# Board_2550.net
KiCad netlist of a schematic drawn in EAGLE
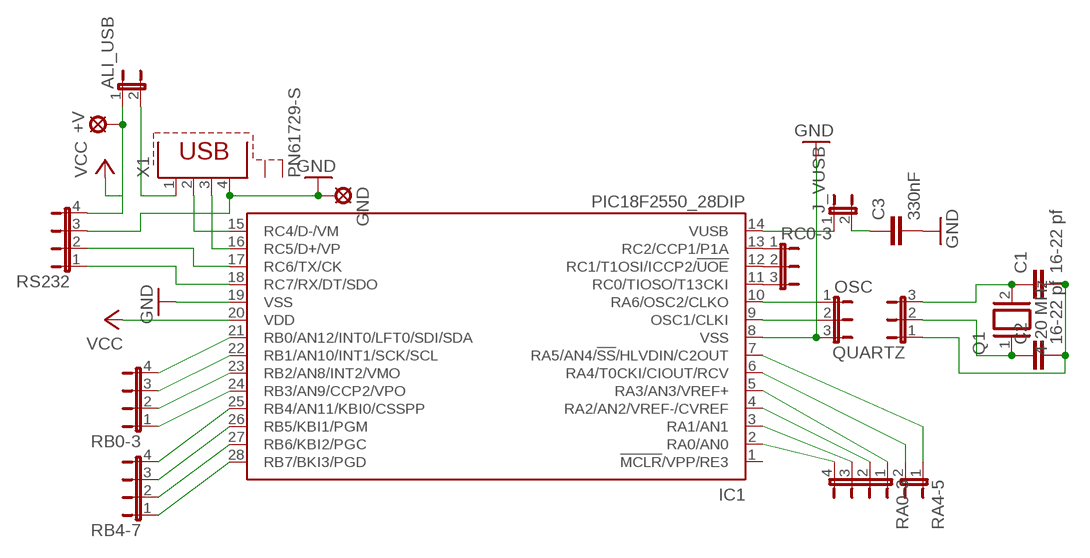
[diagram p0: schematic, sheet 1]

(export (version "E")
  (design (tool "Eeschema 10.0.6"))
  (components
    (comp (ref "+V")
      (value "SE14")
      (footprint "eagle-import:SE14")
      (libsource (lib "eagle-import") (part "SE14"))
    )
    (comp (ref "ALI_USB")
      (value "JP1E")
      (footprint "eagle-import:JP1")
      (libsource (lib "eagle-import") (part "JP1E"))
    )
    (comp (ref "C1")
      (value "16-22 pf")
      (footprint "eagle-import:C025-024X044")
      (libsource (lib "eagle-import") (part "C-EU025-024X044"))
    )
    (comp (ref "C2")
      (value "16-22 pf")
      (footprint "eagle-import:C025-024X044")
      (libsource (lib "eagle-import") (part "C-EU025-024X044"))
    )
    (comp (ref "C3")
      (value "330nF")
      (footprint "eagle-import:C025-024X044")
      (libsource (lib "eagle-import") (part "C-EU025-024X044"))
    )
    (comp (ref "GND")
      (value "SE14")
      (footprint "eagle-import:SE14")
      (libsource (lib "eagle-import") (part "SE14"))
    )
    (comp (ref "IC1")
      (value "PIC18F2550_28DIP")
      (footprint "eagle-import:DIL28-3")
      (fields (field (name "MF") "MICROCHIP") (field (name "MPN") "PIC18F2550-I/SP"))
      (libsource (lib "eagle-import") (part "PIC18F2_28DIP550"))
    )
    (comp (ref "J_VUSB")
      (value "JP1E")
      (footprint "eagle-import:JP1")
      (libsource (lib "eagle-import") (part "JP1E"))
    )
    (comp (ref "OSC")
      (value "JP2E")
      (footprint "eagle-import:JP2")
      (libsource (lib "eagle-import") (part "JP2E"))
    )
    (comp (ref "Q1")
      (value "4-20 MHz")
      (footprint "eagle-import:Q")
      (libsource (lib "eagle-import") (part "XTAL"))
    )
    (comp (ref "QUARTZ")
      (value "JP2W")
      (footprint "eagle-import:JP2W")
      (libsource (lib "eagle-import") (part "JP2W"))
    )
    (comp (ref "RA0-3")
      (value "JP4E")
      (footprint "eagle-import:JP4")
      (libsource (lib "eagle-import") (part "JP4E"))
    )
    (comp (ref "RA4-5")
      (value "JP1E")
      (footprint "eagle-import:JP1")
      (libsource (lib "eagle-import") (part "JP1E"))
    )
    (comp (ref "RB0-3")
      (value "JP4E")
      (footprint "eagle-import:JP4")
      (libsource (lib "eagle-import") (part "JP4E"))
    )
    (comp (ref "RB4-7")
      (value "JP4E")
      (footprint "eagle-import:JP4")
      (libsource (lib "eagle-import") (part "JP4E"))
    )
    (comp (ref "RC0-3")
      (value "JP2E")
      (footprint "eagle-import:JP2")
      (libsource (lib "eagle-import") (part "JP2E"))
    )
    (comp (ref "RS232")
      (value "JP4E")
      (footprint "eagle-import:JP4")
      (libsource (lib "eagle-import") (part "JP4E"))
    )
    (comp (ref "X1")
      (value "PN61729-S")
      (footprint "eagle-import:PN61729-S")
      (libsource (lib "eagle-import") (part "PN61729-S"))
    )
  )
  (nets
    (net (code "1") (name "GND") (class "Default")
      (node (ref "C3") (pin "2") (pinfunction "2_2") (pintype "passive"))
      (node (ref "GND") (pin "MP") (pinfunction "MP_MP") (pintype "passive"))
      (node (ref "IC1") (pin "19") (pinfunction "VSS_19") (pintype "power_in"))
      (node (ref "IC1") (pin "8") (pinfunction "VSS_8") (pintype "power_in"))
      (node (ref "OSC") (pin "3") (pinfunction "3_3") (pintype "passive"))
      (node (ref "RS232") (pin "3") (pinfunction "3_3") (pintype "passive"))
      (node (ref "X1") (pin "4") (pinfunction "4_4") (pintype "passive"))
    )
    (net (code "2") (name "Net-(ALI_USB-Pad2)") (class "Default")
      (node (ref "ALI_USB") (pin "2") (pinfunction "2_2") (pintype "passive"))
      (node (ref "X1") (pin "1") (pinfunction "1_1") (pintype "passive"))
    )
    (net (code "3") (name "Net-(C1-Pad1)") (class "Default")
      (node (ref "C1") (pin "1") (pinfunction "1_1") (pintype "passive"))
      (node (ref "Q1") (pin "2") (pinfunction "2_2") (pintype "passive"))
      (node (ref "QUARTZ") (pin "3") (pinfunction "3_3") (pintype "passive"))
    )
    (net (code "4") (name "Net-(C1-Pad2)") (class "Default")
      (node (ref "C1") (pin "2") (pinfunction "2_2") (pintype "passive"))
      (node (ref "C2") (pin "2") (pinfunction "2_2") (pintype "passive"))
      (node (ref "QUARTZ") (pin "1") (pinfunction "1_1") (pintype "passive"))
    )
    (net (code "5") (name "Net-(C2-Pad1)") (class "Default")
      (node (ref "C2") (pin "1") (pinfunction "1_1") (pintype "passive"))
      (node (ref "Q1") (pin "1") (pinfunction "1_1") (pintype "passive"))
      (node (ref "QUARTZ") (pin "2") (pinfunction "2_2") (pintype "passive"))
    )
    (net (code "6") (name "Net-(C3-Pad1)") (class "Default")
      (node (ref "C3") (pin "1") (pinfunction "1_1") (pintype "passive"))
      (node (ref "J_VUSB") (pin "2") (pinfunction "2_2") (pintype "passive"))
    )
    (net (code "7") (name "Net-(IC1-OSC1{slash}CLKI)") (class "Default")
      (node (ref "IC1") (pin "9") (pinfunction "OSC1/CLKI_9") (pintype "input"))
      (node (ref "OSC") (pin "2") (pinfunction "2_2") (pintype "passive"))
    )
    (net (code "8") (name "Net-(IC1-RA0{slash}AN0)") (class "Default")
      (node (ref "IC1") (pin "2") (pinfunction "RA0/AN0_2") (pintype "bidirectional"))
      (node (ref "RA0-3") (pin "4") (pinfunction "4_4") (pintype "passive"))
    )
    (net (code "9") (name "Net-(IC1-RA1{slash}AN1)") (class "Default")
      (node (ref "IC1") (pin "3") (pinfunction "RA1/AN1_3") (pintype "bidirectional"))
      (node (ref "RA0-3") (pin "3") (pinfunction "3_3") (pintype "passive"))
    )
    (net (code "10") (name "Net-(IC1-RA2{slash}AN2{slash}VREF-{slash}CVREF)") (class "Default")
      (node (ref "IC1") (pin "4") (pinfunction "RA2/AN2/VREF-/CVREF_4") (pintype "bidirectional"))
      (node (ref "RA0-3") (pin "2") (pinfunction "2_2") (pintype "passive"))
    )
    (net (code "11") (name "Net-(IC1-RA3{slash}AN3{slash}VREF+)") (class "Default")
      (node (ref "IC1") (pin "5") (pinfunction "RA3/AN3/VREF+_5") (pintype "bidirectional"))
      (node (ref "RA0-3") (pin "1") (pinfunction "1_1") (pintype "passive"))
    )
    (net (code "12") (name "Net-(IC1-RA4{slash}T0CKI{slash}CIOUT{slash}RCV)") (class "Default")
      (node (ref "IC1") (pin "6") (pinfunction "RA4/T0CKI/CIOUT/RCV_6") (pintype "bidirectional"))
      (node (ref "RA4-5") (pin "2") (pinfunction "2_2") (pintype "passive"))
    )
    (net (code "13") (name "Net-(IC1-RA5{slash}AN4{slash}~{SS}{slash}HLVDIN{slash}C2OUT)") (class "Default")
      (node (ref "IC1") (pin "7") (pinfunction "RA5/AN4/~{SS}/HLVDIN/C2OUT_7") (pintype "bidirectional"))
      (node (ref "RA4-5") (pin "1") (pinfunction "1_1") (pintype "passive"))
    )
    (net (code "14") (name "Net-(IC1-RA6{slash}OSC2{slash}CLKO)") (class "Default")
      (node (ref "IC1") (pin "10") (pinfunction "RA6/OSC2/CLKO_10") (pintype "output"))
      (node (ref "OSC") (pin "1") (pinfunction "1_1") (pintype "passive"))
    )
    (net (code "15") (name "Net-(IC1-RB0{slash}AN12{slash}INT0{slash}LFT0{slash}SDI{slash}SDA)") (class "Default")
      (node (ref "IC1") (pin "21") (pinfunction "RB0/AN12/INT0/LFT0/SDI/SDA_21") (pintype "bidirectional"))
      (node (ref "RB0-3") (pin "4") (pinfunction "4_4") (pintype "passive"))
    )
    (net (code "16") (name "Net-(IC1-RB1{slash}AN10{slash}INT1{slash}SCK{slash}SCL)") (class "Default")
      (node (ref "IC1") (pin "22") (pinfunction "RB1/AN10/INT1/SCK/SCL_22") (pintype "bidirectional"))
      (node (ref "RB0-3") (pin "3") (pinfunction "3_3") (pintype "passive"))
    )
    (net (code "17") (name "Net-(IC1-RB2{slash}AN8{slash}INT2{slash}VMO)") (class "Default")
      (node (ref "IC1") (pin "23") (pinfunction "RB2/AN8/INT2/VMO_23") (pintype "bidirectional"))
      (node (ref "RB0-3") (pin "2") (pinfunction "2_2") (pintype "passive"))
    )
    (net (code "18") (name "Net-(IC1-RB3{slash}AN9{slash}CCP2{slash}VPO)") (class "Default")
      (node (ref "IC1") (pin "24") (pinfunction "RB3/AN9/CCP2/VPO_24") (pintype "bidirectional"))
      (node (ref "RB0-3") (pin "1") (pinfunction "1_1") (pintype "passive"))
    )
    (net (code "19") (name "Net-(IC1-RB4{slash}AN11{slash}KBI0{slash}CSSPP)") (class "Default")
      (node (ref "IC1") (pin "25") (pinfunction "RB4/AN11/KBI0/CSSPP_25") (pintype "bidirectional"))
      (node (ref "RB4-7") (pin "4") (pinfunction "4_4") (pintype "passive"))
    )
    (net (code "20") (name "Net-(IC1-RB5{slash}KBI1{slash}PGM)") (class "Default")
      (node (ref "IC1") (pin "26") (pinfunction "RB5/KBI1/PGM_26") (pintype "bidirectional"))
      (node (ref "RB4-7") (pin "3") (pinfunction "3_3") (pintype "passive"))
    )
    (net (code "21") (name "Net-(IC1-RB6{slash}KBI2{slash}PGC)") (class "Default")
      (node (ref "IC1") (pin "27") (pinfunction "RB6/KBI2/PGC_27") (pintype "bidirectional"))
      (node (ref "RB4-7") (pin "2") (pinfunction "2_2") (pintype "passive"))
    )
    (net (code "22") (name "Net-(IC1-RB7{slash}BKI3{slash}PGD)") (class "Default")
      (node (ref "IC1") (pin "28") (pinfunction "RB7/BKI3/PGD_28") (pintype "bidirectional"))
      (node (ref "RB4-7") (pin "1") (pinfunction "1_1") (pintype "passive"))
    )
    (net (code "23") (name "Net-(IC1-RC0{slash}TIOSO{slash}T13CKI)") (class "Default")
      (node (ref "IC1") (pin "11") (pinfunction "RC0/TIOSO/T13CKI_11") (pintype "bidirectional"))
      (node (ref "RC0-3") (pin "3") (pinfunction "3_3") (pintype "passive"))
    )
    (net (code "24") (name "Net-(IC1-RC1{slash}T1OSI{slash}ICCP2{slash}~{UOE})") (class "Default")
      (node (ref "IC1") (pin "12") (pinfunction "RC1/T1OSI/ICCP2/~{UOE}_12") (pintype "bidirectional"))
      (node (ref "RC0-3") (pin "2") (pinfunction "2_2") (pintype "passive"))
    )
    (net (code "25") (name "Net-(IC1-RC2{slash}CCP1{slash}P1A)") (class "Default")
      (node (ref "IC1") (pin "13") (pinfunction "RC2/CCP1/P1A_13") (pintype "bidirectional"))
      (node (ref "RC0-3") (pin "1") (pinfunction "1_1") (pintype "passive"))
    )
    (net (code "26") (name "Net-(IC1-RC4{slash}D-{slash}VM)") (class "Default")
      (node (ref "IC1") (pin "15") (pinfunction "RC4/D-/VM_15") (pintype "bidirectional"))
      (node (ref "X1") (pin "2") (pinfunction "2_2") (pintype "passive"))
    )
    (net (code "27") (name "Net-(IC1-RC5{slash}D+{slash}VP)") (class "Default")
      (node (ref "IC1") (pin "16") (pinfunction "RC5/D+/VP_16") (pintype "bidirectional"))
      (node (ref "X1") (pin "3") (pinfunction "3_3") (pintype "passive"))
    )
    (net (code "28") (name "Net-(IC1-RC6{slash}TX{slash}CK)") (class "Default")
      (node (ref "IC1") (pin "17") (pinfunction "RC6/TX/CK_17") (pintype "bidirectional"))
      (node (ref "RS232") (pin "2") (pinfunction "2_2") (pintype "passive"))
    )
    (net (code "29") (name "Net-(IC1-RC7{slash}RX{slash}DT{slash}SDO)") (class "Default")
      (node (ref "IC1") (pin "18") (pinfunction "RC7/RX/DT/SDO_18") (pintype "bidirectional"))
      (node (ref "RS232") (pin "1") (pinfunction "1_1") (pintype "passive"))
    )
    (net (code "30") (name "Net-(IC1-VUSB)") (class "Default")
      (node (ref "IC1") (pin "14") (pinfunction "VUSB_14") (pintype "bidirectional"))
      (node (ref "J_VUSB") (pin "1") (pinfunction "1_1") (pintype "passive"))
    )
    (net (code "31") (name "VCC") (class "Default")
      (node (ref "+V") (pin "MP") (pinfunction "MP_MP") (pintype "passive"))
      (node (ref "ALI_USB") (pin "1") (pinfunction "1_1") (pintype "passive"))
      (node (ref "IC1") (pin "20") (pinfunction "VDD_20") (pintype "power_in"))
      (node (ref "RS232") (pin "4") (pinfunction "4_4") (pintype "passive"))
    )
    (net (code "32") (name "unconnected-(IC1-~{MCLR}{slash}VPP{slash}RE3-Pad1)") (class "Default")
      (node (ref "IC1") (pin "1") (pinfunction "~{MCLR}/VPP/RE3_1") (pintype "input"))
    )
    (net (code "33") (name "unconnected-(X1-PadS1)") (class "Default")
      (node (ref "X1") (pin "S1") (pinfunction "S1_S1") (pintype "passive"))
    )
    (net (code "34") (name "unconnected-(X1-PadS2)") (class "Default")
      (node (ref "X1") (pin "S2") (pinfunction "S2_S2") (pintype "passive"))
    )
  )
)
